# OPA188.net
KiCad netlist of a schematic drawn in EAGLE
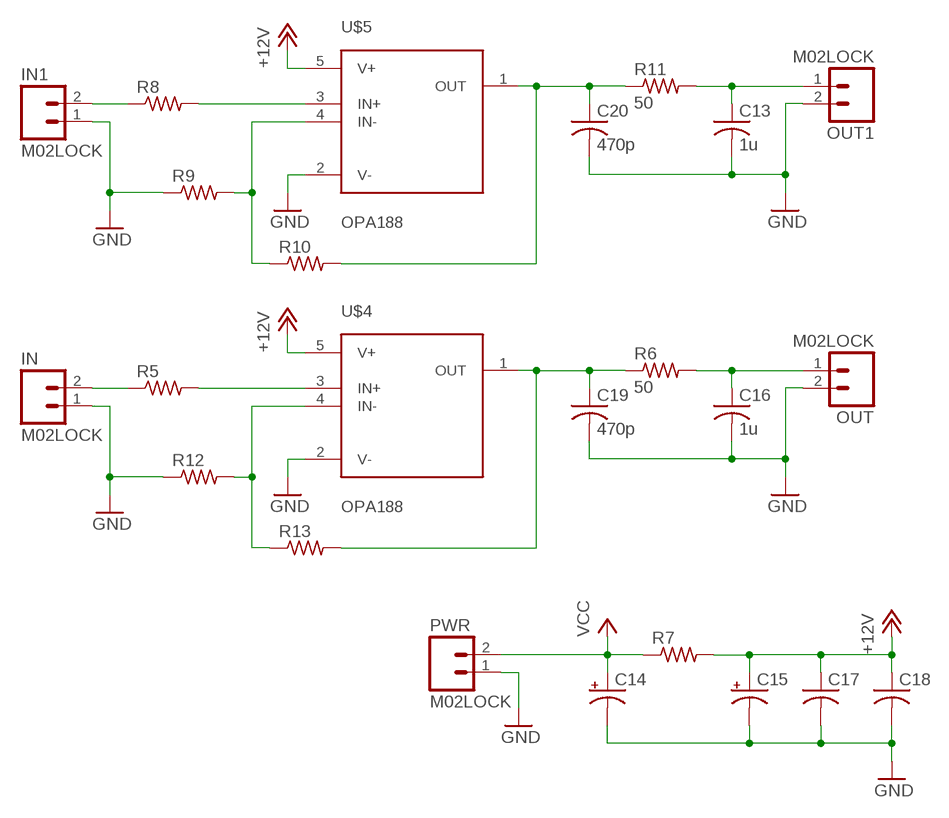
[diagram p0: schematic, sheet 2]

(export (version "E")
  (design (tool "Eeschema 10.0.6"))
  (components
    (comp (ref "C13")
      (value "1u")
      (footprint "eagle-import:C0805")
      (libsource (lib "eagle-import") (part "C-USC0805"))
    )
    (comp (ref "C14")
      (value "CPOL-US")
      (footprint "eagle-import:SMD_6.6X6.6")
      (libsource (lib "eagle-import") (part "CPOL-US"))
    )
    (comp (ref "C15")
      (value "CPOL-US")
      (footprint "eagle-import:SMD_6.6X6.6")
      (libsource (lib "eagle-import") (part "CPOL-US"))
    )
    (comp (ref "C16")
      (value "1u")
      (footprint "eagle-import:C0805")
      (libsource (lib "eagle-import") (part "C-USC0805"))
    )
    (comp (ref "C17")
      (value "C-USC0805")
      (footprint "eagle-import:C0805")
      (libsource (lib "eagle-import") (part "C-USC0805"))
    )
    (comp (ref "C18")
      (value "C-USC0805")
      (footprint "eagle-import:C0805")
      (libsource (lib "eagle-import") (part "C-USC0805"))
    )
    (comp (ref "C19")
      (value "470p")
      (footprint "eagle-import:C0805")
      (libsource (lib "eagle-import") (part "C-USC0805"))
    )
    (comp (ref "C20")
      (value "470p")
      (footprint "eagle-import:C0805")
      (libsource (lib "eagle-import") (part "C-USC0805"))
    )
    (comp (ref "IN")
      (value "M02LOCK")
      (footprint "eagle-import:1X02_LOCK")
      (libsource (lib "eagle-import") (part "M02LOCK"))
    )
    (comp (ref "IN1")
      (value "M02LOCK")
      (footprint "eagle-import:1X02_LOCK")
      (libsource (lib "eagle-import") (part "M02LOCK"))
    )
    (comp (ref "OUT")
      (value "M02LOCK")
      (footprint "eagle-import:1X02_LOCK")
      (libsource (lib "eagle-import") (part "M02LOCK"))
    )
    (comp (ref "OUT1")
      (value "M02LOCK")
      (footprint "eagle-import:1X02_LOCK")
      (libsource (lib "eagle-import") (part "M02LOCK"))
    )
    (comp (ref "PWR")
      (value "M02LOCK")
      (footprint "eagle-import:1X02_LOCK")
      (libsource (lib "eagle-import") (part "M02LOCK"))
    )
    (comp (ref "R5")
      (value "R-US_R0805")
      (footprint "eagle-import:R0805")
      (libsource (lib "eagle-import") (part "R-US_R0805"))
    )
    (comp (ref "R6")
      (value "50")
      (footprint "eagle-import:R0805")
      (libsource (lib "eagle-import") (part "R-US_R0805"))
    )
    (comp (ref "R7")
      (value "R-US_R1206")
      (footprint "eagle-import:R1206")
      (libsource (lib "eagle-import") (part "R-US_R1206"))
    )
    (comp (ref "R8")
      (value "R-US_R0805")
      (footprint "eagle-import:R0805")
      (libsource (lib "eagle-import") (part "R-US_R0805"))
    )
    (comp (ref "R9")
      (value "R-US_R0805")
      (footprint "eagle-import:R0805")
      (libsource (lib "eagle-import") (part "R-US_R0805"))
    )
    (comp (ref "R10")
      (value "R-US_R0805")
      (footprint "eagle-import:R0805")
      (libsource (lib "eagle-import") (part "R-US_R0805"))
    )
    (comp (ref "R11")
      (value "50")
      (footprint "eagle-import:R0805")
      (libsource (lib "eagle-import") (part "R-US_R0805"))
    )
    (comp (ref "R12")
      (value "R-US_R0805")
      (footprint "eagle-import:R0805")
      (libsource (lib "eagle-import") (part "R-US_R0805"))
    )
    (comp (ref "R13")
      (value "R-US_R0805")
      (footprint "eagle-import:R0805")
      (libsource (lib "eagle-import") (part "R-US_R0805"))
    )
    (comp (ref "U$4")
      (value "OPA188")
      (footprint "eagle-import:SOT23-DBV")
      (libsource (lib "eagle-import") (part "OPA188"))
    )
    (comp (ref "U$5")
      (value "OPA188")
      (footprint "eagle-import:SOT23-DBV")
      (libsource (lib "eagle-import") (part "OPA188"))
    )
  )
  (nets
    (net (code "1") (name "+12V") (class "Default")
      (node (ref "C15") (pin "+") (pinfunction "+_+") (pintype "passive"))
      (node (ref "C17") (pin "1") (pinfunction "1_1") (pintype "passive"))
      (node (ref "C18") (pin "1") (pinfunction "1_1") (pintype "passive"))
      (node (ref "R7") (pin "2") (pinfunction "2_2") (pintype "passive"))
      (node (ref "U$4") (pin "5") (pinfunction "V+_5") (pintype "power_in"))
      (node (ref "U$5") (pin "5") (pinfunction "V+_5") (pintype "power_in"))
    )
    (net (code "2") (name "GND") (class "Default")
      (node (ref "C13") (pin "2") (pinfunction "2_2") (pintype "passive"))
      (node (ref "C14") (pin "-") (pinfunction "-_-") (pintype "passive"))
      (node (ref "C15") (pin "-") (pinfunction "-_-") (pintype "passive"))
      (node (ref "C16") (pin "2") (pinfunction "2_2") (pintype "passive"))
      (node (ref "C17") (pin "2") (pinfunction "2_2") (pintype "passive"))
      (node (ref "C18") (pin "2") (pinfunction "2_2") (pintype "passive"))
      (node (ref "C19") (pin "2") (pinfunction "2_2") (pintype "passive"))
      (node (ref "C20") (pin "2") (pinfunction "2_2") (pintype "passive"))
      (node (ref "IN") (pin "1") (pinfunction "1_1") (pintype "passive"))
      (node (ref "IN1") (pin "1") (pinfunction "1_1") (pintype "passive"))
      (node (ref "OUT") (pin "2") (pinfunction "2_2") (pintype "passive"))
      (node (ref "OUT1") (pin "2") (pinfunction "2_2") (pintype "passive"))
      (node (ref "PWR") (pin "1") (pinfunction "1_1") (pintype "passive"))
      (node (ref "R12") (pin "1") (pinfunction "1_1") (pintype "passive"))
      (node (ref "R9") (pin "1") (pinfunction "1_1") (pintype "passive"))
      (node (ref "U$4") (pin "2") (pinfunction "V-_2") (pintype "power_in"))
      (node (ref "U$5") (pin "2") (pinfunction "V-_2") (pintype "power_in"))
    )
    (net (code "3") (name "Net-(C13-Pad1)") (class "Default")
      (node (ref "C13") (pin "1") (pinfunction "1_1") (pintype "passive"))
      (node (ref "OUT1") (pin "1") (pinfunction "1_1") (pintype "passive"))
      (node (ref "R11") (pin "2") (pinfunction "2_2") (pintype "passive"))
    )
    (net (code "4") (name "Net-(C16-Pad1)") (class "Default")
      (node (ref "C16") (pin "1") (pinfunction "1_1") (pintype "passive"))
      (node (ref "OUT") (pin "1") (pinfunction "1_1") (pintype "passive"))
      (node (ref "R6") (pin "2") (pinfunction "2_2") (pintype "passive"))
    )
    (net (code "5") (name "Net-(IN-Pad2)") (class "Default")
      (node (ref "IN") (pin "2") (pinfunction "2_2") (pintype "passive"))
      (node (ref "R5") (pin "1") (pinfunction "1_1") (pintype "passive"))
    )
    (net (code "6") (name "Net-(IN1-Pad2)") (class "Default")
      (node (ref "IN1") (pin "2") (pinfunction "2_2") (pintype "passive"))
      (node (ref "R8") (pin "1") (pinfunction "1_1") (pintype "passive"))
    )
    (net (code "7") (name "Net-(U$4-IN+)") (class "Default")
      (node (ref "R5") (pin "2") (pinfunction "2_2") (pintype "passive"))
      (node (ref "U$4") (pin "3") (pinfunction "IN+_3") (pintype "input"))
    )
    (net (code "8") (name "Net-(U$4-IN-)") (class "Default")
      (node (ref "R12") (pin "2") (pinfunction "2_2") (pintype "passive"))
      (node (ref "R13") (pin "1") (pinfunction "1_1") (pintype "passive"))
      (node (ref "U$4") (pin "4") (pinfunction "IN-_4") (pintype "input"))
    )
    (net (code "9") (name "Net-(U$4-OUT)") (class "Default")
      (node (ref "C19") (pin "1") (pinfunction "1_1") (pintype "passive"))
      (node (ref "R13") (pin "2") (pinfunction "2_2") (pintype "passive"))
      (node (ref "R6") (pin "1") (pinfunction "1_1") (pintype "passive"))
      (node (ref "U$4") (pin "1") (pinfunction "OUT_1") (pintype "output"))
    )
    (net (code "10") (name "Net-(U$5-IN+)") (class "Default")
      (node (ref "R8") (pin "2") (pinfunction "2_2") (pintype "passive"))
      (node (ref "U$5") (pin "3") (pinfunction "IN+_3") (pintype "input"))
    )
    (net (code "11") (name "Net-(U$5-IN-)") (class "Default")
      (node (ref "R10") (pin "1") (pinfunction "1_1") (pintype "passive"))
      (node (ref "R9") (pin "2") (pinfunction "2_2") (pintype "passive"))
      (node (ref "U$5") (pin "4") (pinfunction "IN-_4") (pintype "input"))
    )
    (net (code "12") (name "Net-(U$5-OUT)") (class "Default")
      (node (ref "C20") (pin "1") (pinfunction "1_1") (pintype "passive"))
      (node (ref "R10") (pin "2") (pinfunction "2_2") (pintype "passive"))
      (node (ref "R11") (pin "1") (pinfunction "1_1") (pintype "passive"))
      (node (ref "U$5") (pin "1") (pinfunction "OUT_1") (pintype "output"))
    )
    (net (code "13") (name "VCC") (class "Default")
      (node (ref "C14") (pin "+") (pinfunction "+_+") (pintype "passive"))
      (node (ref "PWR") (pin "2") (pinfunction "2_2") (pintype "passive"))
      (node (ref "R7") (pin "1") (pinfunction "1_1") (pintype "passive"))
    )
  )
)
